# Power_Supply_Current_Limit.net
KiCad netlist of a schematic drawn in Altium Designer
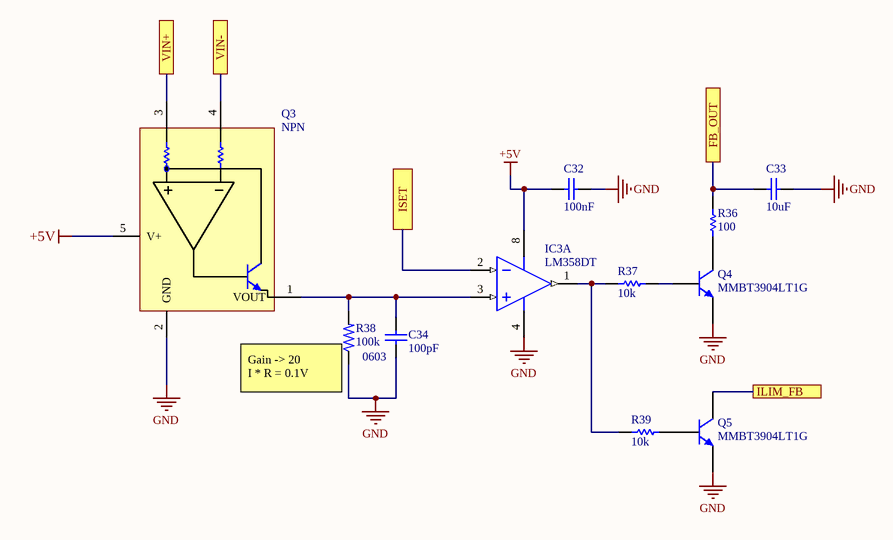
[diagram p0: Power_Supply_Current_Limit.SchDoc]

(export (version "E")
  (design (tool "Eeschema 10.0.6"))
  (components
    (comp (ref "C32")
      (value "100nF")
      (footprint "CAPC1608X09N")
      (description "0603 10 nF 50 V ± 10% Tolerance X7R Surface Mount Multilayer Ceramic Capacitor")
      (fields
        (field (name "MANUFACTURE PART NUMBER") "CC0603KRX7R9BB104")
        (field (name "MANUFACTURER") "YAGEO")
      )
      (libsource (lib "POWER CARD") (part "CMP-2f55e5122ad9f092-5"))
    )
    (comp (ref "C33")
      (value "10uF")
      (footprint "CAPC3216X127X50ML20T25")
      (description "CAP CER 0.1UF 100V 10% X7R 1206")
      (fields
        (field (name "MANUFACTURER") "Samsung Electro-Mechanics")
        (field (name "MANUFACTURE PART NUMBER") "CL31B106KBHNNNE")
      )
      (libsource (lib "POWER CARD") (part "CMP-126371-4"))
    )
    (comp (ref "C34")
      (value "100pF")
      (footprint "CAPC1608X09N")
      (description "0603 10 nF 50 V ± 10% Tolerance X7R Surface Mount Multilayer Ceramic Capacitor")
      (fields
        (field (name "MANUFACTURE PART NUMBER") "0603N101J500CT")
        (field (name "MANUFACTURER") "Walsin Tech Corp")
      )
      (libsource (lib "POWER CARD") (part "CMP-2f55e5122ad9f092-5"))
    )
    (comp (ref "IC3")
      (value "LM358DT")
      (footprint "SOIC-OA8_M")
      (description "LM358 Series 30 V 1.1 MHz Low Power Dual Operational Amplifier - SOIC-8")
      (fields (field (name "MANUFACTURER") "STMicroelectronics"))
      (libsource (lib "POWER CARD") (part "CMP-9a3c516d515145fb-3"))
    )
    (comp (ref "Q3")
      (value "NPN")
      (footprint "PCB-h3r3bzz71pyabhalkrge-1")
      (description "36-V, High-Side, Current Output Current Shunt Monitor 5-SOT-23 -40 to 125")
      (fields
        (field (name "MANUFACTURE PART NUMBER") "INA138NA/3K")
        (field (name "MANUFACTURER") "Texas Instruments")
      )
      (libsource (lib "POWER CARD") (part "CMP-0019c915bbf2dfde-3"))
    )
    (comp (ref "Q4")
      (value "MMBT3904LT1G")
      (footprint "SOT-23")
      (description "MMBT Series 40 V 200 mA SMT NPN Silicon General Purpose Transistor - SOT-23")
      (fields (field (name "MANUFACTURER") "ON Semiconductor"))
      (libsource (lib "POWER CARD") (part "CMP-857799-8"))
    )
    (comp (ref "Q5")
      (value "MMBT3904LT1G")
      (footprint "SOT-23")
      (description "MMBT Series 40 V 200 mA SMT NPN Silicon General Purpose Transistor - SOT-23")
      (fields (field (name "MANUFACTURER") "ON Semiconductor"))
      (libsource (lib "POWER CARD") (part "CMP-857799-8"))
    )
    (comp (ref "R36")
      (value "100")
      (footprint "gen0603-2")
      (description "Surface Mount Thick Film Resistor, RC Series, 1 kohm, 100 mW, - 1%, 50 V, 0603 [1608 Metric]")
      (fields
        (field (name "MANUFACTURER") "UNI-ROYAL(Uniroyal Elec)")
        (field (name "MANUFACTURE PART NUMBER") "0603WAF1000T5E")
      )
      (libsource (lib "POWER CARD") (part "CMP-1853278-27"))
    )
    (comp (ref "R37")
      (value "10k")
      (footprint "gen0603-2")
      (description "Surface Mount Thick Film Resistor, RC Series, 1 kohm, 100 mW, - 1%, 50 V, 0603 [1608 Metric]")
      (fields
        (field (name "MANUFACTURER") "YAGEO")
        (field (name "MANUFACTURE PART NUMBER") "RC0603FR-0710KL")
      )
      (libsource (lib "POWER CARD") (part "CMP-1853278-27"))
    )
    (comp (ref "R38")
      (value "100k")
      (footprint "PCB-3elf45qdqizoabmczrxc-1")
      (description "Surface Mount Thick Film Resistor, RC Series, 1 kohm, 100 mW, - 1%, 50 V, 0603 [1608 Metric]")
      (fields
        (field (name "PACKAGE / CASE") "0603")
        (field (name "MANUFACTURER") "Walsin Tech Corp")
        (field (name "MANUFACTURE PART NUMBER") "WR06X1003FTL")
      )
      (libsource (lib "POWER CARD") (part "CMP-1853278-23"))
    )
    (comp (ref "R39")
      (value "10k")
      (footprint "gen0603-2")
      (description "Surface Mount Thick Film Resistor, RC Series, 1 kohm, 100 mW, - 1%, 50 V, 0603 [1608 Metric]")
      (fields
        (field (name "MANUFACTURER") "YAGEO")
        (field (name "MANUFACTURE PART NUMBER") "RC0603FR-0710KL")
      )
      (libsource (lib "POWER CARD") (part "CMP-1853278-27"))
    )
  )
  (nets
    (net (code "1") (name "+5V") (class "Default")
      (node (ref "C32") (pin "2") (pinfunction "2_2") (pintype "passive"))
      (node (ref "IC3") (pin "8") (pinfunction "VCC_8") (pintype "power_in"))
      (node (ref "Q3") (pin "5") (pinfunction "V+_5") (pintype "passive"))
    )
    (net (code "2") (name "/FB_OUT") (class "Default")
      (node (ref "C33") (pin "2") (pinfunction "2_2") (pintype "passive"))
      (node (ref "R36") (pin "2") (pinfunction "2_2") (pintype "passive"))
    )
    (net (code "3") (name "/ILIM_FB") (class "Default")
      (node (ref "Q5") (pin "3") (pinfunction "C_3") (pintype "passive"))
    )
    (net (code "4") (name "/ISET") (class "Default")
      (node (ref "IC3") (pin "2") (pinfunction "INA-_2") (pintype "input"))
    )
    (net (code "5") (name "/VIN+") (class "Default")
      (node (ref "Q3") (pin "3") (pinfunction "3_3") (pintype "passive"))
    )
    (net (code "6") (name "/VIN-") (class "Default")
      (node (ref "Q3") (pin "4") (pinfunction "4_4") (pintype "passive"))
    )
    (net (code "7") (name "GND") (class "Default")
      (node (ref "C32") (pin "1") (pinfunction "1_1") (pintype "passive"))
      (node (ref "C33") (pin "1") (pinfunction "1_1") (pintype "passive"))
      (node (ref "C34") (pin "1") (pinfunction "1_1") (pintype "passive"))
      (node (ref "IC3") (pin "4") (pinfunction "VEE/GND_4") (pintype "power_in"))
      (node (ref "Q3") (pin "2") (pinfunction "GND_2") (pintype "passive"))
      (node (ref "Q4") (pin "2") (pinfunction "E_2") (pintype "passive"))
      (node (ref "Q5") (pin "2") (pinfunction "E_2") (pintype "passive"))
      (node (ref "R38") (pin "1") (pinfunction "1_1") (pintype "passive"))
    )
    (net (code "8") (name "Net-(IC3A-INA+)") (class "Default")
      (node (ref "C34") (pin "2") (pinfunction "2_2") (pintype "passive"))
      (node (ref "IC3") (pin "3") (pinfunction "INA+_3") (pintype "input"))
      (node (ref "Q3") (pin "1") (pinfunction "VOUT_1") (pintype "passive"))
      (node (ref "R38") (pin "2") (pinfunction "2_2") (pintype "passive"))
    )
    (net (code "9") (name "Net-(IC3A-OUTA)") (class "Default")
      (node (ref "IC3") (pin "1") (pinfunction "OUTA_1") (pintype "output"))
      (node (ref "R37") (pin "2") (pinfunction "2_2") (pintype "passive"))
      (node (ref "R39") (pin "2") (pinfunction "2_2") (pintype "passive"))
    )
    (net (code "10") (name "Net-(Q4-B)") (class "Default")
      (node (ref "Q4") (pin "1") (pinfunction "B_1") (pintype "passive"))
      (node (ref "R37") (pin "1") (pinfunction "1_1") (pintype "passive"))
    )
    (net (code "11") (name "Net-(Q5-B)") (class "Default")
      (node (ref "Q5") (pin "1") (pinfunction "B_1") (pintype "passive"))
      (node (ref "R39") (pin "1") (pinfunction "1_1") (pintype "passive"))
    )
    (net (code "12") (name "unconnected-(Q4-C-Pad3)") (class "Default")
      (node (ref "Q4") (pin "3") (pinfunction "C_3") (pintype "passive"))
    )
    (net (code "13") (name "unconnected-(R36-Pad1)") (class "Default")
      (node (ref "R36") (pin "1") (pinfunction "1_1") (pintype "passive"))
    )
  )
)
